# V3.net
KiCad netlist of a schematic drawn in EAGLE
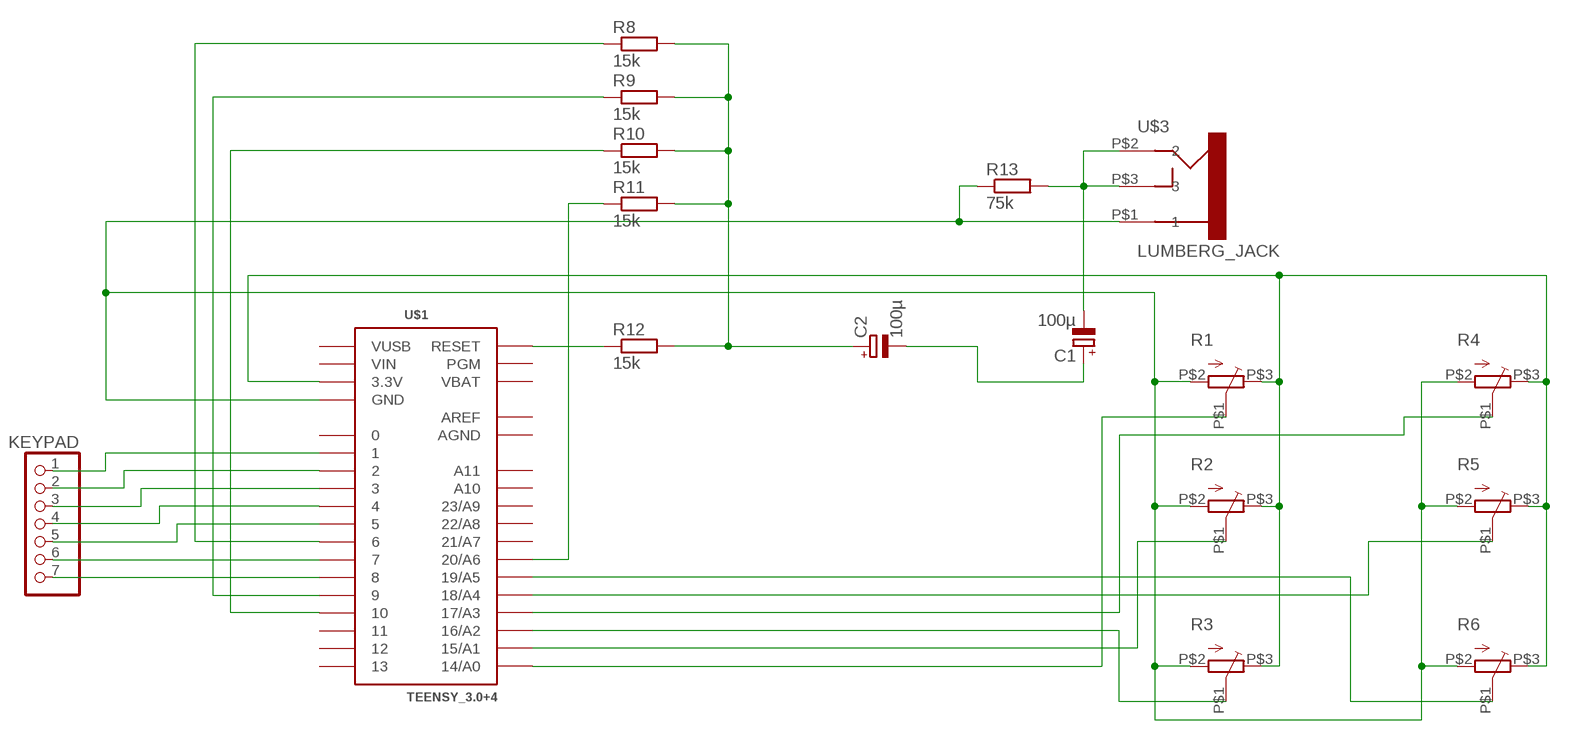
[diagram p0: schematic, sheet 1]

(export (version "E")
  (design (tool "Eeschema 10.0.6"))
  (components
    (comp (ref "C1")
      (value "100µ")
      (footprint "eagle-import:E2,5-6")
      (libsource (lib "eagle-import") (part "CPOL-EUE2.5-6"))
    )
    (comp (ref "C2")
      (value "100µ")
      (footprint "eagle-import:E2,5-6")
      (libsource (lib "eagle-import") (part "CPOL-EUE2.5-6"))
    )
    (comp (ref "KEYPAD")
      (value "PINHD-1X7")
      (footprint "eagle-import:1X07")
      (libsource (lib "eagle-import") (part "PINHD-1X7"))
    )
    (comp (ref "R1")
      (value "STR09K113")
      (footprint "eagle-import:STR09K113")
      (libsource (lib "eagle-import") (part "STR09K113"))
    )
    (comp (ref "R2")
      (value "STR09K113")
      (footprint "eagle-import:STR09K113")
      (libsource (lib "eagle-import") (part "STR09K113"))
    )
    (comp (ref "R3")
      (value "STR09K113")
      (footprint "eagle-import:STR09K113")
      (libsource (lib "eagle-import") (part "STR09K113"))
    )
    (comp (ref "R4")
      (value "STR09K113")
      (footprint "eagle-import:STR09K113")
      (libsource (lib "eagle-import") (part "STR09K113"))
    )
    (comp (ref "R5")
      (value "STR09K113")
      (footprint "eagle-import:STR09K113")
      (libsource (lib "eagle-import") (part "STR09K113"))
    )
    (comp (ref "R6")
      (value "STR09K113")
      (footprint "eagle-import:STR09K113")
      (libsource (lib "eagle-import") (part "STR09K113"))
    )
    (comp (ref "R8")
      (value "15k")
      (footprint "eagle-import:0309_12")
      (libsource (lib "eagle-import") (part "R-EU_0309/12"))
    )
    (comp (ref "R9")
      (value "15k")
      (footprint "eagle-import:0309_12")
      (libsource (lib "eagle-import") (part "R-EU_0309/12"))
    )
    (comp (ref "R10")
      (value "15k")
      (footprint "eagle-import:0309_12")
      (libsource (lib "eagle-import") (part "R-EU_0309/12"))
    )
    (comp (ref "R11")
      (value "15k")
      (footprint "eagle-import:0309_12")
      (libsource (lib "eagle-import") (part "R-EU_0309/12"))
    )
    (comp (ref "R12")
      (value "15k")
      (footprint "eagle-import:0309_12")
      (libsource (lib "eagle-import") (part "R-EU_0309/12"))
    )
    (comp (ref "R13")
      (value "75k")
      (footprint "eagle-import:0309_12")
      (libsource (lib "eagle-import") (part "R-EU_0309/12"))
    )
    (comp (ref "U$1")
      (value "TEENSY_3.0+4")
      (footprint "eagle-import:TEENSY_3.0+4")
      (libsource (lib "eagle-import") (part "TEENSY_3.0+4"))
    )
    (comp (ref "U$3")
      (value "LUMBERG_JACK")
      (footprint "eagle-import:JACK_CON")
      (libsource (lib "eagle-import") (part "LUMBERG_JACK"))
    )
  )
  (nets
    (net (code "1") (name "/AGND") (class "Default")
      (node (ref "U$1") (pin "AGND") (pinfunction "AGND_AGND") (pintype "power_in"))
    )
    (net (code "2") (name "/AREF") (class "Default")
      (node (ref "U$1") (pin "AREF") (pinfunction "AREF_AREF") (pintype "power_in"))
    )
    (net (code "3") (name "/VBAT") (class "Default")
      (node (ref "U$1") (pin "VBAT") (pinfunction "VBAT_VBAT") (pintype "power_in"))
    )
    (net (code "4") (name "/VIN") (class "Default")
      (node (ref "U$1") (pin "VIN") (pinfunction "VIN_VIN") (pintype "power_in"))
    )
    (net (code "5") (name "/VUSB") (class "Default")
      (node (ref "U$1") (pin "VUSB") (pinfunction "VUSB_VUSB") (pintype "power_in"))
    )
    (net (code "6") (name "Net-(C1-Pad+)") (class "Default")
      (node (ref "C1") (pin "+") (pinfunction "+_+") (pintype "passive"))
      (node (ref "C2") (pin "-") (pinfunction "-_-") (pintype "passive"))
    )
    (net (code "7") (name "Net-(C2-Pad+)") (class "Default")
      (node (ref "C2") (pin "+") (pinfunction "+_+") (pintype "passive"))
      (node (ref "R10") (pin "2") (pinfunction "2_2") (pintype "passive"))
      (node (ref "R11") (pin "2") (pinfunction "2_2") (pintype "passive"))
      (node (ref "R12") (pin "2") (pinfunction "2_2") (pintype "passive"))
      (node (ref "R8") (pin "2") (pinfunction "2_2") (pintype "passive"))
      (node (ref "R9") (pin "2") (pinfunction "2_2") (pintype "passive"))
    )
    (net (code "8") (name "Net-(KEYPAD-Pad1)") (class "Default")
      (node (ref "KEYPAD") (pin "1") (pinfunction "1_1") (pintype "passive"))
      (node (ref "U$1") (pin "1") (pinfunction "1_1") (pintype "bidirectional"))
    )
    (net (code "9") (name "Net-(KEYPAD-Pad2)") (class "Default")
      (node (ref "KEYPAD") (pin "2") (pinfunction "2_2") (pintype "passive"))
      (node (ref "U$1") (pin "2") (pinfunction "2_2") (pintype "bidirectional"))
    )
    (net (code "10") (name "Net-(KEYPAD-Pad3)") (class "Default")
      (node (ref "KEYPAD") (pin "3") (pinfunction "3_3") (pintype "passive"))
      (node (ref "U$1") (pin "3") (pinfunction "3_3") (pintype "bidirectional"))
    )
    (net (code "11") (name "Net-(KEYPAD-Pad4)") (class "Default")
      (node (ref "KEYPAD") (pin "4") (pinfunction "4_4") (pintype "passive"))
      (node (ref "U$1") (pin "4") (pinfunction "4_4") (pintype "bidirectional"))
    )
    (net (code "12") (name "Net-(KEYPAD-Pad5)") (class "Default")
      (node (ref "KEYPAD") (pin "5") (pinfunction "5_5") (pintype "passive"))
      (node (ref "U$1") (pin "5") (pinfunction "5_5") (pintype "bidirectional"))
    )
    (net (code "13") (name "Net-(KEYPAD-Pad6)") (class "Default")
      (node (ref "KEYPAD") (pin "6") (pinfunction "6_6") (pintype "passive"))
      (node (ref "U$1") (pin "7") (pinfunction "7_7") (pintype "bidirectional"))
    )
    (net (code "14") (name "Net-(KEYPAD-Pad7)") (class "Default")
      (node (ref "KEYPAD") (pin "7") (pinfunction "7_7") (pintype "passive"))
      (node (ref "U$1") (pin "8") (pinfunction "8_8") (pintype "bidirectional"))
    )
    (net (code "15") (name "Net-(R1-E)") (class "Default")
      (node (ref "R1") (pin "P$3") (pinfunction "E_P$3") (pintype "passive"))
      (node (ref "R2") (pin "P$3") (pinfunction "E_P$3") (pintype "passive"))
      (node (ref "R3") (pin "P$3") (pinfunction "E_P$3") (pintype "passive"))
      (node (ref "R4") (pin "P$3") (pinfunction "E_P$3") (pintype "passive"))
      (node (ref "R5") (pin "P$3") (pinfunction "E_P$3") (pintype "passive"))
      (node (ref "R6") (pin "P$3") (pinfunction "E_P$3") (pintype "passive"))
      (node (ref "U$1") (pin "3.3V") (pinfunction "3.3V_3.3V") (pintype "power_in"))
      (node (ref "U$1") (pin "3.3V1") (pinfunction "3.3V_3.3V1") (pintype "power_in"))
    )
    (net (code "16") (name "Net-(R1-S)") (class "Default")
      (node (ref "R1") (pin "P$2") (pinfunction "S_P$2") (pintype "passive"))
      (node (ref "R13") (pin "1") (pinfunction "1_1") (pintype "passive"))
      (node (ref "R2") (pin "P$2") (pinfunction "S_P$2") (pintype "passive"))
      (node (ref "R3") (pin "P$2") (pinfunction "S_P$2") (pintype "passive"))
      (node (ref "R4") (pin "P$2") (pinfunction "S_P$2") (pintype "passive"))
      (node (ref "R5") (pin "P$2") (pinfunction "S_P$2") (pintype "passive"))
      (node (ref "R6") (pin "P$2") (pinfunction "S_P$2") (pintype "passive"))
      (node (ref "U$1") (pin "GND") (pinfunction "GND_GND") (pintype "power_in"))
      (node (ref "U$1") (pin "GND1") (pinfunction "GND_GND1") (pintype "power_in"))
      (node (ref "U$3") (pin "P$1") (pinfunction "1_P$1") (pintype "passive"))
    )
    (net (code "17") (name "Net-(R1-W)") (class "Default")
      (node (ref "R1") (pin "P$1") (pinfunction "W_P$1") (pintype "passive"))
      (node (ref "U$1") (pin "14/A0") (pinfunction "14/A0_14/A0") (pintype "bidirectional"))
    )
    (net (code "18") (name "Net-(R2-W)") (class "Default")
      (node (ref "R2") (pin "P$1") (pinfunction "W_P$1") (pintype "passive"))
      (node (ref "U$1") (pin "15/A1") (pinfunction "15/A1_15/A1") (pintype "bidirectional"))
    )
    (net (code "19") (name "Net-(R3-W)") (class "Default")
      (node (ref "R3") (pin "P$1") (pinfunction "W_P$1") (pintype "passive"))
      (node (ref "U$1") (pin "16/A2") (pinfunction "16/A2_16/A2") (pintype "bidirectional"))
    )
    (net (code "20") (name "Net-(R4-W)") (class "Default")
      (node (ref "R4") (pin "P$1") (pinfunction "W_P$1") (pintype "passive"))
      (node (ref "U$1") (pin "17/A3") (pinfunction "17/A3_17/A3") (pintype "bidirectional"))
    )
    (net (code "21") (name "Net-(R5-W)") (class "Default")
      (node (ref "R5") (pin "P$1") (pinfunction "W_P$1") (pintype "passive"))
      (node (ref "U$1") (pin "18/A4") (pinfunction "18/A4_18/A4") (pintype "bidirectional"))
    )
    (net (code "22") (name "Net-(R6-W)") (class "Default")
      (node (ref "R6") (pin "P$1") (pinfunction "W_P$1") (pintype "passive"))
      (node (ref "U$1") (pin "19/A5") (pinfunction "19/A5_19/A5") (pintype "bidirectional"))
    )
    (net (code "23") (name "Net-(R8-Pad1)") (class "Default")
      (node (ref "R8") (pin "1") (pinfunction "1_1") (pintype "passive"))
      (node (ref "U$1") (pin "6") (pinfunction "6_6") (pintype "bidirectional"))
    )
    (net (code "24") (name "Net-(R9-Pad1)") (class "Default")
      (node (ref "R9") (pin "1") (pinfunction "1_1") (pintype "passive"))
      (node (ref "U$1") (pin "9") (pinfunction "9_9") (pintype "bidirectional"))
    )
    (net (code "25") (name "Net-(R10-Pad1)") (class "Default")
      (node (ref "R10") (pin "1") (pinfunction "1_1") (pintype "passive"))
      (node (ref "U$1") (pin "10") (pinfunction "10_10") (pintype "bidirectional"))
    )
    (net (code "26") (name "Net-(R11-Pad1)") (class "Default")
      (node (ref "R11") (pin "1") (pinfunction "1_1") (pintype "passive"))
      (node (ref "U$1") (pin "20/A6") (pinfunction "20/A6_20/A6") (pintype "bidirectional"))
    )
    (net (code "27") (name "Net-(R12-Pad1)") (class "Default")
      (node (ref "R12") (pin "1") (pinfunction "1_1") (pintype "passive"))
      (node (ref "U$1") (pin "RESET") (pinfunction "RESET_RESET") (pintype "bidirectional"))
    )
    (net (code "28") (name "Net-(U$3-2)") (class "Default")
      (node (ref "C1") (pin "-") (pinfunction "-_-") (pintype "passive"))
      (node (ref "R13") (pin "2") (pinfunction "2_2") (pintype "passive"))
      (node (ref "U$3") (pin "P$2") (pinfunction "2_P$2") (pintype "passive"))
      (node (ref "U$3") (pin "P$3") (pinfunction "3_P$3") (pintype "passive"))
    )
    (net (code "29") (name "unconnected-(U$1-Pad0)") (class "Default")
      (node (ref "U$1") (pin "0") (pinfunction "0_0") (pintype "bidirectional"))
    )
    (net (code "30") (name "unconnected-(U$1-Pad11)") (class "Default")
      (node (ref "U$1") (pin "11") (pinfunction "11_11") (pintype "bidirectional"))
    )
    (net (code "31") (name "unconnected-(U$1-Pad12)") (class "Default")
      (node (ref "U$1") (pin "12") (pinfunction "12_12") (pintype "bidirectional"))
    )
    (net (code "32") (name "unconnected-(U$1-Pad13)") (class "Default")
      (node (ref "U$1") (pin "13") (pinfunction "13_13") (pintype "bidirectional"))
    )
    (net (code "33") (name "unconnected-(U$1-Pad21{slash}A7)") (class "Default")
      (node (ref "U$1") (pin "21/A7") (pinfunction "21/A7_21/A7") (pintype "bidirectional"))
    )
    (net (code "34") (name "unconnected-(U$1-Pad22{slash}A8)") (class "Default")
      (node (ref "U$1") (pin "22/A8") (pinfunction "22/A8_22/A8") (pintype "bidirectional"))
    )
    (net (code "35") (name "unconnected-(U$1-Pad23{slash}A9)") (class "Default")
      (node (ref "U$1") (pin "23/A9") (pinfunction "23/A9_23/A9") (pintype "bidirectional"))
    )
    (net (code "36") (name "unconnected-(U$1-PadA10)") (class "Default")
      (node (ref "U$1") (pin "A10") (pinfunction "A10_A10") (pintype "bidirectional"))
    )
    (net (code "37") (name "unconnected-(U$1-PadA11)") (class "Default")
      (node (ref "U$1") (pin "A11") (pinfunction "A11_A11") (pintype "bidirectional"))
    )
    (net (code "38") (name "unconnected-(U$1-PadPGM)") (class "Default")
      (node (ref "U$1") (pin "PGM") (pinfunction "PGM_PGM") (pintype "bidirectional"))
    )
  )
)
